# SensorStation_Board_v0_2.net
KiCad netlist of a schematic drawn in EAGLE
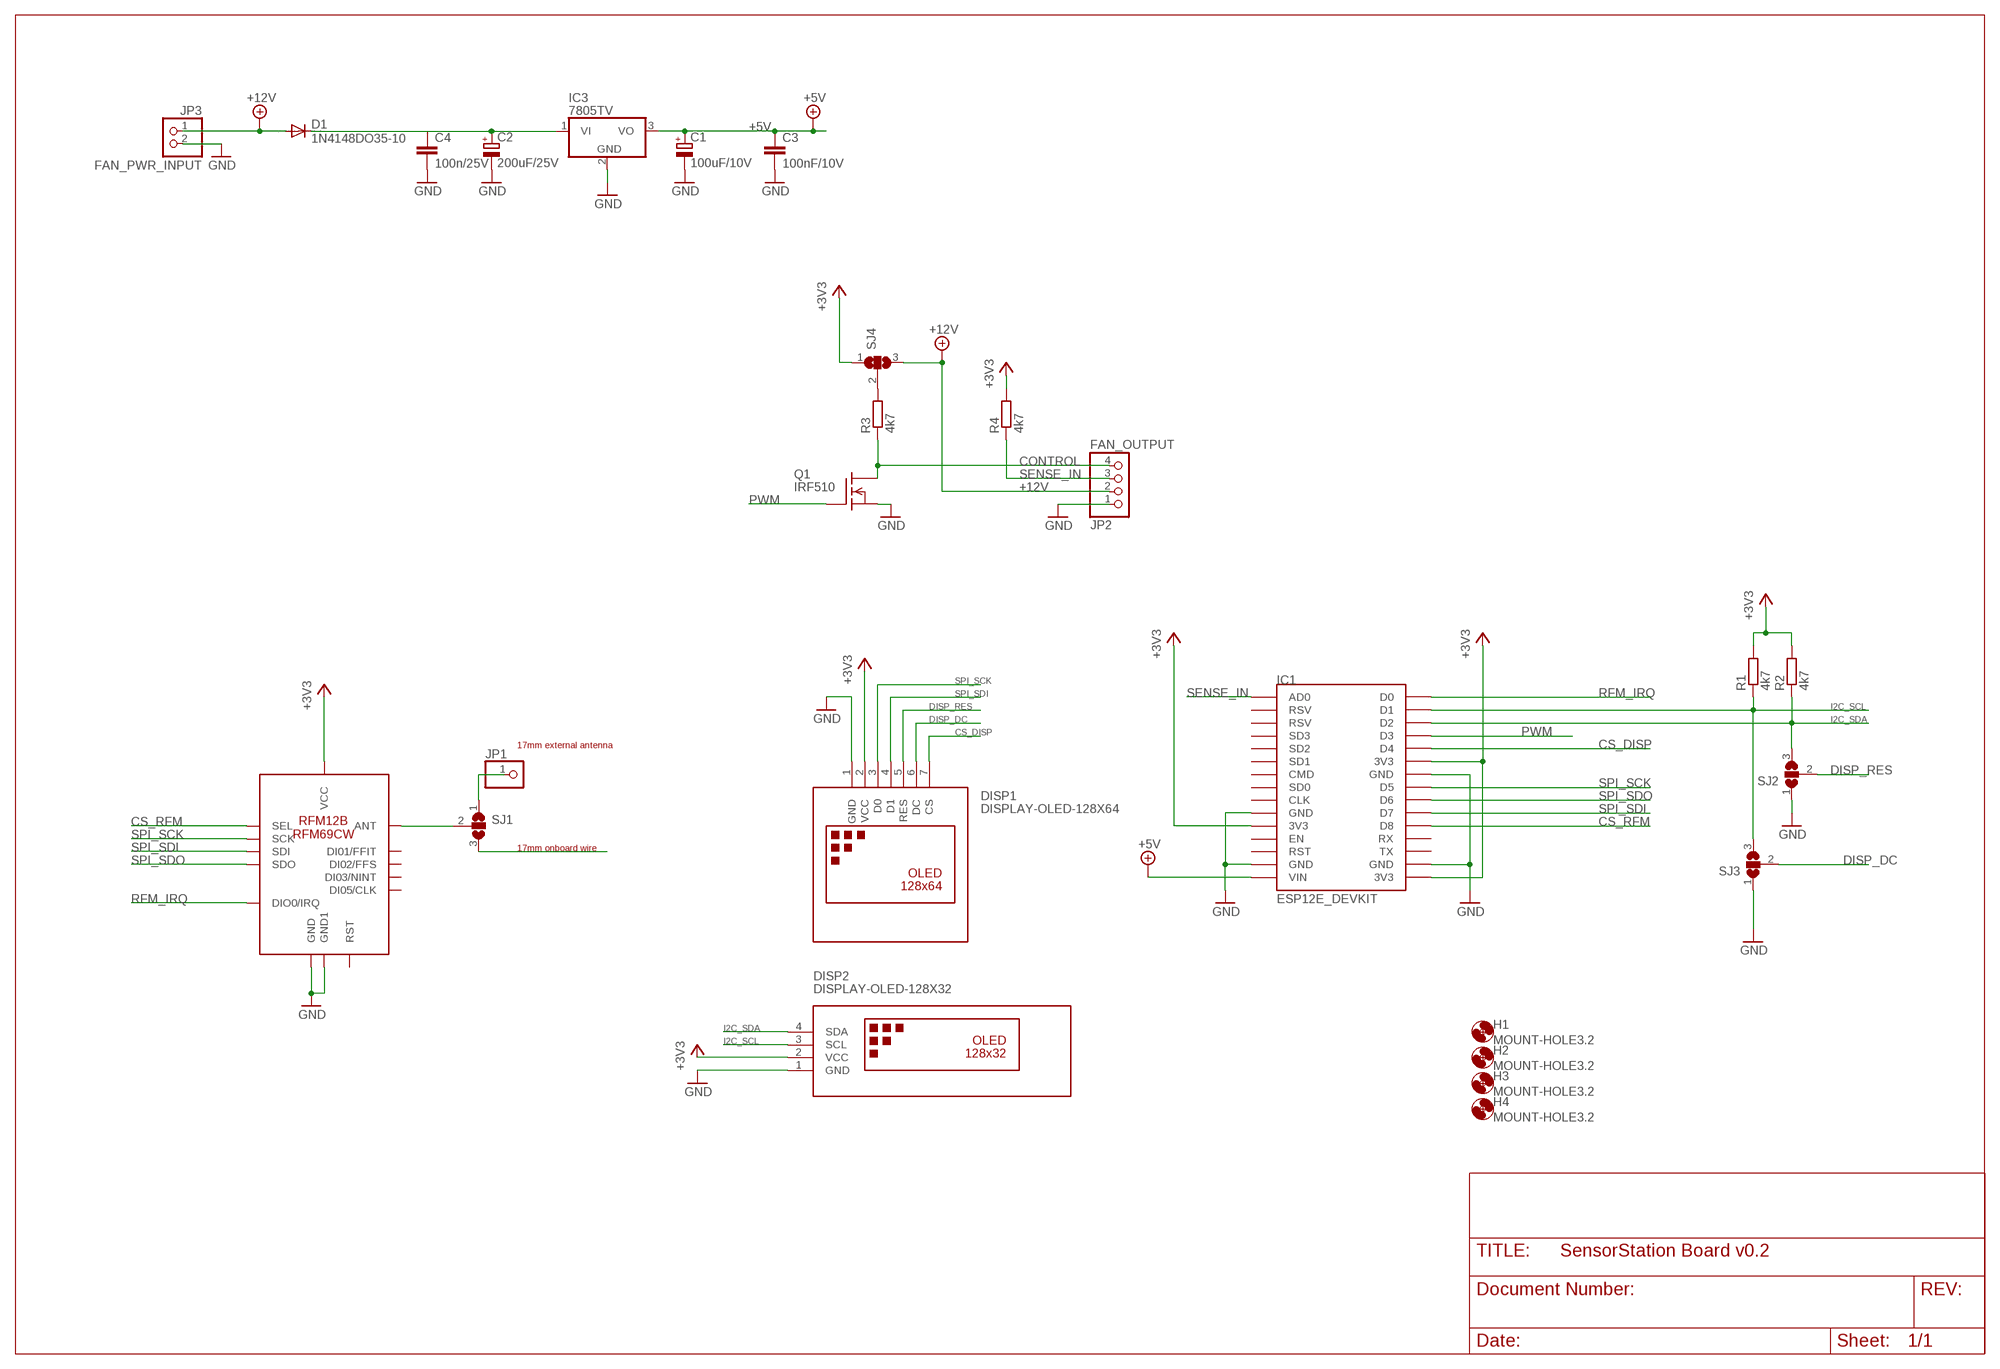
[diagram p0: schematic, sheet 1]

(export (version "E")
  (design (tool "Eeschema 10.0.6"))
  (components
    (comp (ref "C1")
      (value "100uF/10V")
      (footprint "eagle-import:E2,5-6")
      (libsource (lib "eagle-import") (part "CPOL-EUE2.5-6"))
    )
    (comp (ref "C2")
      (value "200uF/25V")
      (footprint "eagle-import:E2,5-6")
      (libsource (lib "eagle-import") (part "CPOL-EUE2.5-6"))
    )
    (comp (ref "C3")
      (value "100nF/10V")
      (footprint "eagle-import:C025-025X050")
      (libsource (lib "eagle-import") (part "C-EU025-025X050"))
    )
    (comp (ref "C4")
      (value "100n/25V")
      (footprint "eagle-import:C025-025X050")
      (libsource (lib "eagle-import") (part "C-EU025-025X050"))
    )
    (comp (ref "D1")
      (value "1N4148DO35-10")
      (footprint "eagle-import:DO35-10")
      (libsource (lib "eagle-import") (part "1N4148DO35-10"))
    )
    (comp (ref "DISP1")
      (value "DISPLAY-OLED-128X64")
      (footprint "eagle-import:DISPLAY-OLED-128X64")
      (libsource (lib "eagle-import") (part "DISPLAY-OLED-128X64"))
    )
    (comp (ref "DISP2")
      (value "DISPLAY-OLED-128X32")
      (footprint "eagle-import:DISPLAY-OLED-128X32")
      (libsource (lib "eagle-import") (part "DISPLAY-OLED-128X32"))
    )
    (comp (ref "H1")
      (value "MOUNT-HOLE3.2")
      (footprint "eagle-import:3,2")
      (libsource (lib "eagle-import") (part "MOUNT-HOLE3.2"))
    )
    (comp (ref "H2")
      (value "MOUNT-HOLE3.2")
      (footprint "eagle-import:3,2")
      (libsource (lib "eagle-import") (part "MOUNT-HOLE3.2"))
    )
    (comp (ref "H3")
      (value "MOUNT-HOLE3.2")
      (footprint "eagle-import:3,2")
      (libsource (lib "eagle-import") (part "MOUNT-HOLE3.2"))
    )
    (comp (ref "H4")
      (value "MOUNT-HOLE3.2")
      (footprint "eagle-import:3,2")
      (libsource (lib "eagle-import") (part "MOUNT-HOLE3.2"))
    )
    (comp (ref "IC1")
      (value "ESP12E_DEVKIT")
      (footprint "eagle-import:ESP12E_DEVKIT")
      (libsource (lib "eagle-import") (part "ESP12E_DEVKIT"))
    )
    (comp (ref "IC2")
      (value "RFM12B/69CW")
      (footprint "eagle-import:RFM12B_69CW")
      (libsource (lib "eagle-import") (part "RFM12B/69CW"))
    )
    (comp (ref "IC3")
      (value "7805TV")
      (footprint "eagle-import:TO220V")
      (libsource (lib "eagle-import") (part "78TV05"))
    )
    (comp (ref "JP1")
      (value "PINHD-1X1")
      (footprint "eagle-import:1X01")
      (libsource (lib "eagle-import") (part "PINHD-1X1"))
    )
    (comp (ref "JP2")
      (value "FAN_OUTPUT")
      (footprint "eagle-import:1X04")
      (libsource (lib "eagle-import") (part "PINHD-1X4"))
    )
    (comp (ref "JP3")
      (value "FAN_PWR_INPUT")
      (footprint "eagle-import:1X02")
      (libsource (lib "eagle-import") (part "PINHD-1X2"))
    )
    (comp (ref "Q1")
      (value "IRF510")
      (footprint "eagle-import:TO220")
      (libsource (lib "eagle-import") (part "IRF510"))
    )
    (comp (ref "R1")
      (value "4k7")
      (footprint "eagle-import:0204_5")
      (libsource (lib "eagle-import") (part "R-EU_0204/5"))
    )
    (comp (ref "R2")
      (value "4k7")
      (footprint "eagle-import:0204_5")
      (libsource (lib "eagle-import") (part "R-EU_0204/5"))
    )
    (comp (ref "R3")
      (value "4k7")
      (footprint "eagle-import:0204_5")
      (libsource (lib "eagle-import") (part "R-EU_0204/5"))
    )
    (comp (ref "R4")
      (value "4k7")
      (footprint "eagle-import:0204_5")
      (libsource (lib "eagle-import") (part "R-EU_0204/5"))
    )
    (comp (ref "SJ1")
      (value "SJ2W")
      (footprint "eagle-import:SJ_2")
      (libsource (lib "eagle-import") (part "SJ2W"))
    )
    (comp (ref "SJ2")
      (value "SJ2W")
      (footprint "eagle-import:SJ_2")
      (libsource (lib "eagle-import") (part "SJ2W"))
    )
    (comp (ref "SJ3")
      (value "SJ2W")
      (footprint "eagle-import:SJ_2")
      (libsource (lib "eagle-import") (part "SJ2W"))
    )
    (comp (ref "SJ4")
      (value "SJ2W")
      (footprint "eagle-import:SJ_2")
      (libsource (lib "eagle-import") (part "SJ2W"))
    )
  )
  (nets
    (net (code "1") (name "+3V3") (class "Default")
      (node (ref "DISP1") (pin "2") (pinfunction "VCC_2") (pintype "power_in"))
      (node (ref "DISP2") (pin "2") (pinfunction "VCC_2") (pintype "power_in"))
      (node (ref "IC1") (pin "3V3@0") (pinfunction "3V3_3V3@0") (pintype "bidirectional"))
      (node (ref "IC1") (pin "3V3@1") (pinfunction "3V3_3V3@1") (pintype "bidirectional"))
      (node (ref "IC1") (pin "3V3@2") (pinfunction "3V3_3V3@2") (pintype "bidirectional"))
      (node (ref "IC2") (pin "VDD") (pinfunction "VCC_VDD") (pintype "power_in"))
      (node (ref "R1") (pin "2") (pinfunction "2_2") (pintype "passive"))
      (node (ref "R2") (pin "2") (pinfunction "2_2") (pintype "passive"))
      (node (ref "R4") (pin "2") (pinfunction "2_2") (pintype "passive"))
      (node (ref "SJ4") (pin "1") (pinfunction "1_1") (pintype "passive"))
    )
    (net (code "2") (name "+5V") (class "Default")
      (node (ref "C1") (pin "+") (pinfunction "+_+") (pintype "passive"))
      (node (ref "C3") (pin "1") (pinfunction "1_1") (pintype "passive"))
      (node (ref "IC1") (pin "VIN") (pinfunction "VIN_VIN") (pintype "bidirectional"))
      (node (ref "IC3") (pin "3") (pinfunction "VO_3") (pintype "passive"))
    )
    (net (code "3") (name "+12V") (class "Default")
      (node (ref "D1") (pin "A") (pinfunction "A_A") (pintype "passive"))
      (node (ref "JP2") (pin "2") (pinfunction "2_2") (pintype "passive"))
      (node (ref "JP3") (pin "1") (pinfunction "1_1") (pintype "passive"))
      (node (ref "SJ4") (pin "3") (pinfunction "3_3") (pintype "passive"))
    )
    (net (code "4") (name "/CONTROL") (class "Default")
      (node (ref "JP2") (pin "4") (pinfunction "4_4") (pintype "passive"))
      (node (ref "Q1") (pin "2") (pinfunction "D_2") (pintype "passive"))
      (node (ref "R3") (pin "1") (pinfunction "1_1") (pintype "passive"))
    )
    (net (code "5") (name "/CS_DISP") (class "Default")
      (node (ref "DISP1") (pin "7") (pinfunction "CS_7") (pintype "bidirectional"))
      (node (ref "IC1") (pin "D4") (pinfunction "D4_D4") (pintype "bidirectional"))
    )
    (net (code "6") (name "/CS_RFM") (class "Default")
      (node (ref "IC1") (pin "D8") (pinfunction "D8_D8") (pintype "bidirectional"))
      (node (ref "IC2") (pin "SEL") (pinfunction "SEL_SEL") (pintype "input"))
    )
    (net (code "7") (name "/DISP_DC") (class "Default")
      (node (ref "DISP1") (pin "6") (pinfunction "DC_6") (pintype "bidirectional"))
      (node (ref "SJ3") (pin "2") (pinfunction "2_2") (pintype "passive"))
    )
    (net (code "8") (name "/DISP_RES") (class "Default")
      (node (ref "DISP1") (pin "5") (pinfunction "RES_5") (pintype "bidirectional"))
      (node (ref "SJ2") (pin "2") (pinfunction "2_2") (pintype "passive"))
    )
    (net (code "9") (name "/I2C_SCL") (class "Default")
      (node (ref "DISP2") (pin "3") (pinfunction "SCL_3") (pintype "bidirectional"))
      (node (ref "IC1") (pin "D1") (pinfunction "D1_D1") (pintype "bidirectional"))
      (node (ref "R1") (pin "1") (pinfunction "1_1") (pintype "passive"))
      (node (ref "SJ3") (pin "3") (pinfunction "3_3") (pintype "passive"))
    )
    (net (code "10") (name "/I2C_SDA") (class "Default")
      (node (ref "DISP2") (pin "4") (pinfunction "SDA_4") (pintype "bidirectional"))
      (node (ref "IC1") (pin "D2") (pinfunction "D2_D2") (pintype "bidirectional"))
      (node (ref "R2") (pin "1") (pinfunction "1_1") (pintype "passive"))
      (node (ref "SJ2") (pin "3") (pinfunction "3_3") (pintype "passive"))
    )
    (net (code "11") (name "/PWM") (class "Default")
      (node (ref "IC1") (pin "D3") (pinfunction "D3_D3") (pintype "bidirectional"))
      (node (ref "Q1") (pin "1") (pinfunction "G_1") (pintype "passive"))
    )
    (net (code "12") (name "/RFM_IRQ") (class "Default")
      (node (ref "IC1") (pin "D0") (pinfunction "D0_D0") (pintype "bidirectional"))
      (node (ref "IC2") (pin "IRQ") (pinfunction "DIO0/IRQ_IRQ") (pintype "open_collector"))
    )
    (net (code "13") (name "/SENSE_IN") (class "Default")
      (node (ref "IC1") (pin "AD0") (pinfunction "AD0_AD0") (pintype "bidirectional"))
      (node (ref "JP2") (pin "3") (pinfunction "3_3") (pintype "passive"))
      (node (ref "R4") (pin "1") (pinfunction "1_1") (pintype "passive"))
    )
    (net (code "14") (name "/SPI_SCK") (class "Default")
      (node (ref "DISP1") (pin "3") (pinfunction "D0_3") (pintype "bidirectional"))
      (node (ref "IC1") (pin "D5") (pinfunction "D5_D5") (pintype "bidirectional"))
      (node (ref "IC2") (pin "SCK") (pinfunction "SCK_SCK") (pintype "input"))
    )
    (net (code "15") (name "/SPI_SDI") (class "Default")
      (node (ref "DISP1") (pin "4") (pinfunction "D1_4") (pintype "bidirectional"))
      (node (ref "IC1") (pin "D7") (pinfunction "D7_D7") (pintype "bidirectional"))
      (node (ref "IC2") (pin "SDI") (pinfunction "SDI_SDI") (pintype "input"))
    )
    (net (code "16") (name "/SPI_SDO") (class "Default")
      (node (ref "IC1") (pin "D6") (pinfunction "D6_D6") (pintype "bidirectional"))
      (node (ref "IC2") (pin "SDO") (pinfunction "SDO_SDO") (pintype "output"))
    )
    (net (code "17") (name "GND") (class "Default")
      (node (ref "C1") (pin "-") (pinfunction "-_-") (pintype "passive"))
      (node (ref "C2") (pin "-") (pinfunction "-_-") (pintype "passive"))
      (node (ref "C3") (pin "2") (pinfunction "2_2") (pintype "passive"))
      (node (ref "C4") (pin "2") (pinfunction "2_2") (pintype "passive"))
      (node (ref "DISP1") (pin "1") (pinfunction "GND_1") (pintype "power_in"))
      (node (ref "DISP2") (pin "1") (pinfunction "GND_1") (pintype "power_in"))
      (node (ref "IC1") (pin "GND@0") (pinfunction "GND_GND@0") (pintype "bidirectional"))
      (node (ref "IC1") (pin "GND@1") (pinfunction "GND_GND@1") (pintype "bidirectional"))
      (node (ref "IC1") (pin "GND@2") (pinfunction "GND_GND@2") (pintype "bidirectional"))
      (node (ref "IC1") (pin "GND@3") (pinfunction "GND_GND@3") (pintype "bidirectional"))
      (node (ref "IC2") (pin "GND") (pinfunction "GND_GND") (pintype "power_in"))
      (node (ref "IC2") (pin "GND1") (pinfunction "GND1_GND1") (pintype "power_in"))
      (node (ref "IC3") (pin "2") (pinfunction "GND_2") (pintype "passive"))
      (node (ref "JP2") (pin "1") (pinfunction "1_1") (pintype "passive"))
      (node (ref "JP3") (pin "2") (pinfunction "2_2") (pintype "passive"))
      (node (ref "Q1") (pin "3") (pinfunction "S_3") (pintype "passive"))
      (node (ref "SJ2") (pin "1") (pinfunction "1_1") (pintype "passive"))
      (node (ref "SJ3") (pin "1") (pinfunction "1_1") (pintype "passive"))
    )
    (net (code "18") (name "Net-(IC2-PadANT)") (class "Default")
      (node (ref "IC2") (pin "ANT") (pinfunction "ANT_ANT") (pintype "passive"))
      (node (ref "SJ1") (pin "2") (pinfunction "2_2") (pintype "passive"))
    )
    (net (code "19") (name "Net-(IC3-VI)") (class "Default")
      (node (ref "C2") (pin "+") (pinfunction "+_+") (pintype "passive"))
      (node (ref "C4") (pin "1") (pinfunction "1_1") (pintype "passive"))
      (node (ref "D1") (pin "C") (pinfunction "C_C") (pintype "passive"))
      (node (ref "IC3") (pin "1") (pinfunction "VI_1") (pintype "input"))
    )
    (net (code "20") (name "Net-(JP1-Pad1)") (class "Default")
      (node (ref "JP1") (pin "1") (pinfunction "1_1") (pintype "passive"))
      (node (ref "SJ1") (pin "1") (pinfunction "1_1") (pintype "passive"))
    )
    (net (code "21") (name "Net-(R3-Pad2)") (class "Default")
      (node (ref "R3") (pin "2") (pinfunction "2_2") (pintype "passive"))
      (node (ref "SJ4") (pin "2") (pinfunction "2_2") (pintype "passive"))
    )
    (net (code "22") (name "unconnected-(IC1-PadCLK)") (class "Default")
      (node (ref "IC1") (pin "CLK") (pinfunction "CLK_CLK") (pintype "bidirectional"))
    )
    (net (code "23") (name "unconnected-(IC1-PadCMD)") (class "Default")
      (node (ref "IC1") (pin "CMD") (pinfunction "CMD_CMD") (pintype "bidirectional"))
    )
    (net (code "24") (name "unconnected-(IC1-PadEN)") (class "Default")
      (node (ref "IC1") (pin "EN") (pinfunction "EN_EN") (pintype "bidirectional"))
    )
    (net (code "25") (name "unconnected-(IC1-PadRST)") (class "Default")
      (node (ref "IC1") (pin "RST") (pinfunction "RST_RST") (pintype "bidirectional"))
    )
    (net (code "26") (name "unconnected-(IC1-PadRX)") (class "Default")
      (node (ref "IC1") (pin "RX") (pinfunction "RX_RX") (pintype "bidirectional"))
    )
    (net (code "27") (name "unconnected-(IC1-PadSD0)") (class "Default")
      (node (ref "IC1") (pin "SD0") (pinfunction "SD0_SD0") (pintype "bidirectional"))
    )
    (net (code "28") (name "unconnected-(IC1-PadSD1)") (class "Default")
      (node (ref "IC1") (pin "SD1") (pinfunction "SD1_SD1") (pintype "bidirectional"))
    )
    (net (code "29") (name "unconnected-(IC1-PadSD2)") (class "Default")
      (node (ref "IC1") (pin "SD2") (pinfunction "SD2_SD2") (pintype "bidirectional"))
    )
    (net (code "30") (name "unconnected-(IC1-PadSD3)") (class "Default")
      (node (ref "IC1") (pin "SD3") (pinfunction "SD3_SD3") (pintype "bidirectional"))
    )
    (net (code "31") (name "unconnected-(IC1-PadTX)") (class "Default")
      (node (ref "IC1") (pin "TX") (pinfunction "TX_TX") (pintype "bidirectional"))
    )
    (net (code "32") (name "unconnected-(IC1-RSV-PadRSV@0)") (class "Default")
      (node (ref "IC1") (pin "RSV@0") (pinfunction "RSV_RSV@0") (pintype "bidirectional"))
    )
    (net (code "33") (name "unconnected-(IC1-RSV-PadRSV@1)") (class "Default")
      (node (ref "IC1") (pin "RSV@1") (pinfunction "RSV_RSV@1") (pintype "bidirectional"))
    )
    (net (code "34") (name "unconnected-(IC2-DI01{slash}FFIT-PadFFIT)") (class "Default")
      (node (ref "IC2") (pin "FFIT") (pinfunction "DI01/FFIT_FFIT") (pintype "passive"))
    )
    (net (code "35") (name "unconnected-(IC2-DI02{slash}FFS-PadFFS)") (class "Default")
      (node (ref "IC2") (pin "FFS") (pinfunction "DI02/FFS_FFS") (pintype "bidirectional"))
    )
    (net (code "36") (name "unconnected-(IC2-DI03{slash}NINT-PadNINT)") (class "Default")
      (node (ref "IC2") (pin "NINT") (pinfunction "DI03/NINT_NINT") (pintype "passive"))
    )
    (net (code "37") (name "unconnected-(IC2-DI05{slash}CLK-PadCLK)") (class "Default")
      (node (ref "IC2") (pin "CLK") (pinfunction "DI05/CLK_CLK") (pintype "passive"))
    )
    (net (code "38") (name "unconnected-(IC2-PadRST)") (class "Default")
      (node (ref "IC2") (pin "RST") (pinfunction "RST_RST") (pintype "open_collector"))
    )
    (net (code "39") (name "unconnected-(SJ1-Pad3)") (class "Default")
      (node (ref "SJ1") (pin "3") (pinfunction "3_3") (pintype "passive"))
    )
  )
)
